# design.net
KiCad netlist of a schematic drawn in Altium Designer
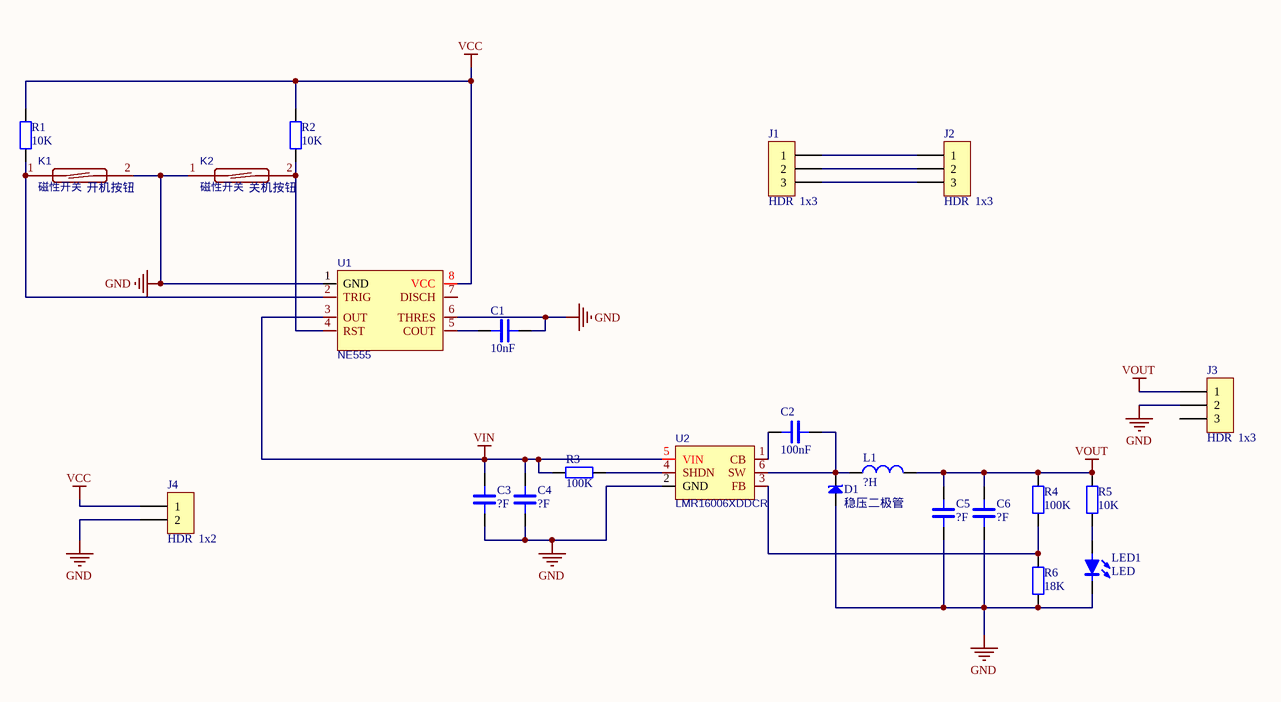
[diagram p0: 自锁降压模块.SchDoc]

(export (version "E")
  (design (tool "Eeschema 10.0.6"))
  (components
    (comp (ref "C1")
      (value "10nF")
      (footprint "0603_C")
      (description "Capacitor")
      (libsource (lib "General") (part "CAP"))
    )
    (comp (ref "C2")
      (value "100nF")
      (footprint "0603_C")
      (description "Capacitor")
      (libsource (lib "General") (part "CAP"))
    )
    (comp (ref "C3")
      (value "?F")
      (footprint "1206_C")
      (description "Capacitor")
      (libsource (lib "General") (part "CAP"))
    )
    (comp (ref "C4")
      (value "?F")
      (footprint "1206_C")
      (description "Capacitor")
      (libsource (lib "General") (part "CAP"))
    )
    (comp (ref "C5")
      (value "?F")
      (footprint "1206_C")
      (description "Capacitor")
      (libsource (lib "General") (part "CAP"))
    )
    (comp (ref "C6")
      (value "?F")
      (footprint "1206_C")
      (description "Capacitor")
      (libsource (lib "General") (part "CAP"))
    )
    (comp (ref "D1") (value "稳压二极管") (footprint "SOD-323") (libsource (lib "General") (part "稳压二极管")))
    (comp (ref "J1")
      (value "HDR  1x3")
      (footprint "排针排母 3P 2.54mm")
      (description "Connector")
      (libsource (lib "General（旧）") (part "HDR  1x3"))
    )
    (comp (ref "J2")
      (value "HDR  1x3")
      (footprint "排针排母 3P 2.54mm")
      (description "Connector")
      (libsource (lib "") (part "HDR  1x3_1"))
    )
    (comp (ref "J3")
      (value "HDR  1x3")
      (footprint "排针排母 3P 2.54mm")
      (description "Connector")
      (libsource (lib "General") (part "HDR  1x3"))
    )
    (comp (ref "J4")
      (value "HDR  1x2")
      (footprint "排针排母 2P 2.54mm")
      (description "Connector")
      (libsource (lib "General（旧）") (part "HDR  1x2"))
    )
    (comp (ref "K1")
      (value "磁性开关")
      (footprint "MKA14103")
      (description "开关")
      (fields
        (field (name "BOM_SUPPLIER PART") "C575284")
        (field (name "BOM_MANUFACTURER PART") "KSK-SME560-1015")
        (field (name "CONTRIBUTOR") "LCSC")
      )
      (libsource (lib "General") (part "干簧管"))
    )
    (comp (ref "K2")
      (value "磁性开关")
      (footprint "MKA14103")
      (description "开关")
      (fields
        (field (name "BOM_SUPPLIER PART") "C575284")
        (field (name "BOM_MANUFACTURER PART") "KSK-SME560-1015")
        (field (name "CONTRIBUTOR") "LCSC")
      )
      (libsource (lib "General") (part "干簧管"))
    )
    (comp (ref "L1")
      (value "?H")
      (footprint "SMD_7*7*4MM")
      (description "Inductor")
      (fields (field (name "PUBLISHER") "Altium Limited"))
      (libsource (lib "General") (part "Inductor"))
    )
    (comp (ref "LED1") (value "LED") (footprint "LED_0603") (libsource (lib "General") (part "LED")))
    (comp (ref "R1")
      (value "10K")
      (footprint "0603_R")
      (description "Resistor")
      (libsource (lib "") (part "RES_1"))
    )
    (comp (ref "R2")
      (value "10K")
      (footprint "0603_R")
      (description "Resistor")
      (libsource (lib "") (part "RES_1"))
    )
    (comp (ref "R3")
      (value "100K")
      (footprint "0603_R")
      (description "Resistor")
      (libsource (lib "General") (part "RES"))
    )
    (comp (ref "R4")
      (value "100K")
      (footprint "0603_R")
      (description "Resistor")
      (libsource (lib "") (part "RES_1"))
    )
    (comp (ref "R5")
      (value "10K")
      (footprint "0603_R")
      (description "Resistor")
      (libsource (lib "") (part "RES_1"))
    )
    (comp (ref "R6")
      (value "18K")
      (footprint "0603_R")
      (description "Resistor")
      (libsource (lib "") (part "RES_1"))
    )
    (comp (ref "U1")
      (value "NE555")
      (footprint "SOP8")
      (description "NE555（世上最牛逼的芯片）")
      (fields (field (name "BOM_MANUFACTURER PART") "NE555P") (field (name "BOM_SUPPLIER PART") "C46749"))
      (libsource (lib "General") (part "NE555"))
    )
    (comp (ref "U2")
      (value "LMR16006XDDCR")
      (footprint "SOT-23-6")
      (description "DC-DC降压模块")
      (fields (field (name "BOM_SUPPLIER PART") "C87080"))
      (libsource (lib "General") (part "LMR16006XDDCR"))
    )
  )
  (nets
    (net (code "1") (name "GND") (class "Default")
      (node (ref "C1") (pin "2") (pinfunction "2_2") (pintype "passive"))
      (node (ref "C3") (pin "1") (pinfunction "1_1") (pintype "passive"))
      (node (ref "C4") (pin "1") (pinfunction "1_1") (pintype "passive"))
      (node (ref "C5") (pin "1") (pinfunction "1_1") (pintype "passive"))
      (node (ref "C6") (pin "1") (pinfunction "1_1") (pintype "passive"))
      (node (ref "D1") (pin "1") (pinfunction "A_1") (pintype "passive"))
      (node (ref "J3") (pin "2") (pinfunction "2_2") (pintype "passive"))
      (node (ref "J4") (pin "2") (pinfunction "2_2") (pintype "passive"))
      (node (ref "K1") (pin "2") (pinfunction "2_2") (pintype "passive"))
      (node (ref "K2") (pin "1") (pinfunction "1_1") (pintype "passive"))
      (node (ref "LED1") (pin "2") (pinfunction "C_2") (pintype "passive"))
      (node (ref "R6") (pin "1") (pinfunction "1_1") (pintype "passive"))
      (node (ref "U1") (pin "1") (pinfunction "GND_1") (pintype "passive"))
      (node (ref "U1") (pin "6") (pinfunction "THRES_6") (pintype "passive"))
      (node (ref "U2") (pin "2") (pinfunction "GND_2") (pintype "passive"))
    )
    (net (code "2") (name "Net-(D1-K)") (class "Default")
      (node (ref "C2") (pin "2") (pinfunction "2_2") (pintype "passive"))
      (node (ref "D1") (pin "2") (pinfunction "K_2") (pintype "passive"))
      (node (ref "L1") (pin "1") (pinfunction "1_1") (pintype "passive"))
      (node (ref "U2") (pin "6") (pinfunction "SW_6") (pintype "passive"))
    )
    (net (code "3") (name "Net-(J1-Pad1)") (class "Default")
      (node (ref "J1") (pin "1") (pinfunction "1_1") (pintype "passive"))
      (node (ref "J2") (pin "1") (pinfunction "1_1") (pintype "passive"))
    )
    (net (code "4") (name "Net-(J1-Pad2)") (class "Default")
      (node (ref "J1") (pin "2") (pinfunction "2_2") (pintype "passive"))
      (node (ref "J2") (pin "2") (pinfunction "2_2") (pintype "passive"))
    )
    (net (code "5") (name "Net-(J1-Pad3)") (class "Default")
      (node (ref "J1") (pin "3") (pinfunction "3_3") (pintype "passive"))
      (node (ref "J2") (pin "3") (pinfunction "3_3") (pintype "passive"))
    )
    (net (code "6") (name "Net-(LED1-A)") (class "Default")
      (node (ref "LED1") (pin "1") (pinfunction "A_1") (pintype "passive"))
      (node (ref "R5") (pin "1") (pinfunction "1_1") (pintype "passive"))
    )
    (net (code "7") (name "Net-(U1-COUT)") (class "Default")
      (node (ref "C1") (pin "1") (pinfunction "1_1") (pintype "passive"))
      (node (ref "U1") (pin "5") (pinfunction "COUT_5") (pintype "passive"))
    )
    (net (code "8") (name "Net-(U1-RST)") (class "Default")
      (node (ref "K2") (pin "2") (pinfunction "2_2") (pintype "passive"))
      (node (ref "R2") (pin "1") (pinfunction "1_1") (pintype "passive"))
      (node (ref "U1") (pin "4") (pinfunction "RST_4") (pintype "passive"))
    )
    (net (code "9") (name "Net-(U1-TRIG)") (class "Default")
      (node (ref "K1") (pin "1") (pinfunction "1_1") (pintype "passive"))
      (node (ref "R1") (pin "1") (pinfunction "1_1") (pintype "passive"))
      (node (ref "U1") (pin "2") (pinfunction "TRIG_2") (pintype "passive"))
    )
    (net (code "10") (name "Net-(U2-CB)") (class "Default")
      (node (ref "C2") (pin "1") (pinfunction "1_1") (pintype "passive"))
      (node (ref "U2") (pin "1") (pinfunction "CB_1") (pintype "passive"))
    )
    (net (code "11") (name "Net-(U2-FB)") (class "Default")
      (node (ref "R4") (pin "1") (pinfunction "1_1") (pintype "passive"))
      (node (ref "R6") (pin "2") (pinfunction "2_2") (pintype "passive"))
      (node (ref "U2") (pin "3") (pinfunction "FB_3") (pintype "passive"))
    )
    (net (code "12") (name "Net-(U2-SHDN)") (class "Default")
      (node (ref "R3") (pin "1") (pinfunction "1_1") (pintype "passive"))
      (node (ref "U2") (pin "4") (pinfunction "SHDN_4") (pintype "passive"))
    )
    (net (code "13") (name "VCC") (class "Default")
      (node (ref "J4") (pin "1") (pinfunction "1_1") (pintype "passive"))
      (node (ref "R1") (pin "2") (pinfunction "2_2") (pintype "passive"))
      (node (ref "R2") (pin "2") (pinfunction "2_2") (pintype "passive"))
      (node (ref "U1") (pin "8") (pinfunction "VCC_8") (pintype "passive"))
    )
    (net (code "14") (name "VIN") (class "Default")
      (node (ref "C3") (pin "2") (pinfunction "2_2") (pintype "passive"))
      (node (ref "C4") (pin "2") (pinfunction "2_2") (pintype "passive"))
      (node (ref "R3") (pin "2") (pinfunction "2_2") (pintype "passive"))
      (node (ref "U1") (pin "3") (pinfunction "OUT_3") (pintype "passive"))
      (node (ref "U2") (pin "5") (pinfunction "VIN_5") (pintype "passive"))
    )
    (net (code "15") (name "VOUT") (class "Default")
      (node (ref "C5") (pin "2") (pinfunction "2_2") (pintype "passive"))
      (node (ref "C6") (pin "2") (pinfunction "2_2") (pintype "passive"))
      (node (ref "J3") (pin "1") (pinfunction "1_1") (pintype "passive"))
      (node (ref "L1") (pin "2") (pinfunction "2_2") (pintype "passive"))
      (node (ref "R4") (pin "2") (pinfunction "2_2") (pintype "passive"))
      (node (ref "R5") (pin "2") (pinfunction "2_2") (pintype "passive"))
    )
    (net (code "16") (name "unconnected-(J3-Pad3)") (class "Default")
      (node (ref "J3") (pin "3") (pinfunction "3_3") (pintype "passive"))
    )
    (net (code "17") (name "unconnected-(U1-DISCH-Pad7)") (class "Default")
      (node (ref "U1") (pin "7") (pinfunction "DISCH_7") (pintype "passive"))
    )
  )
)
